# BuzzerWithRelay.net
KiCad netlist of a schematic drawn in Altium Designer
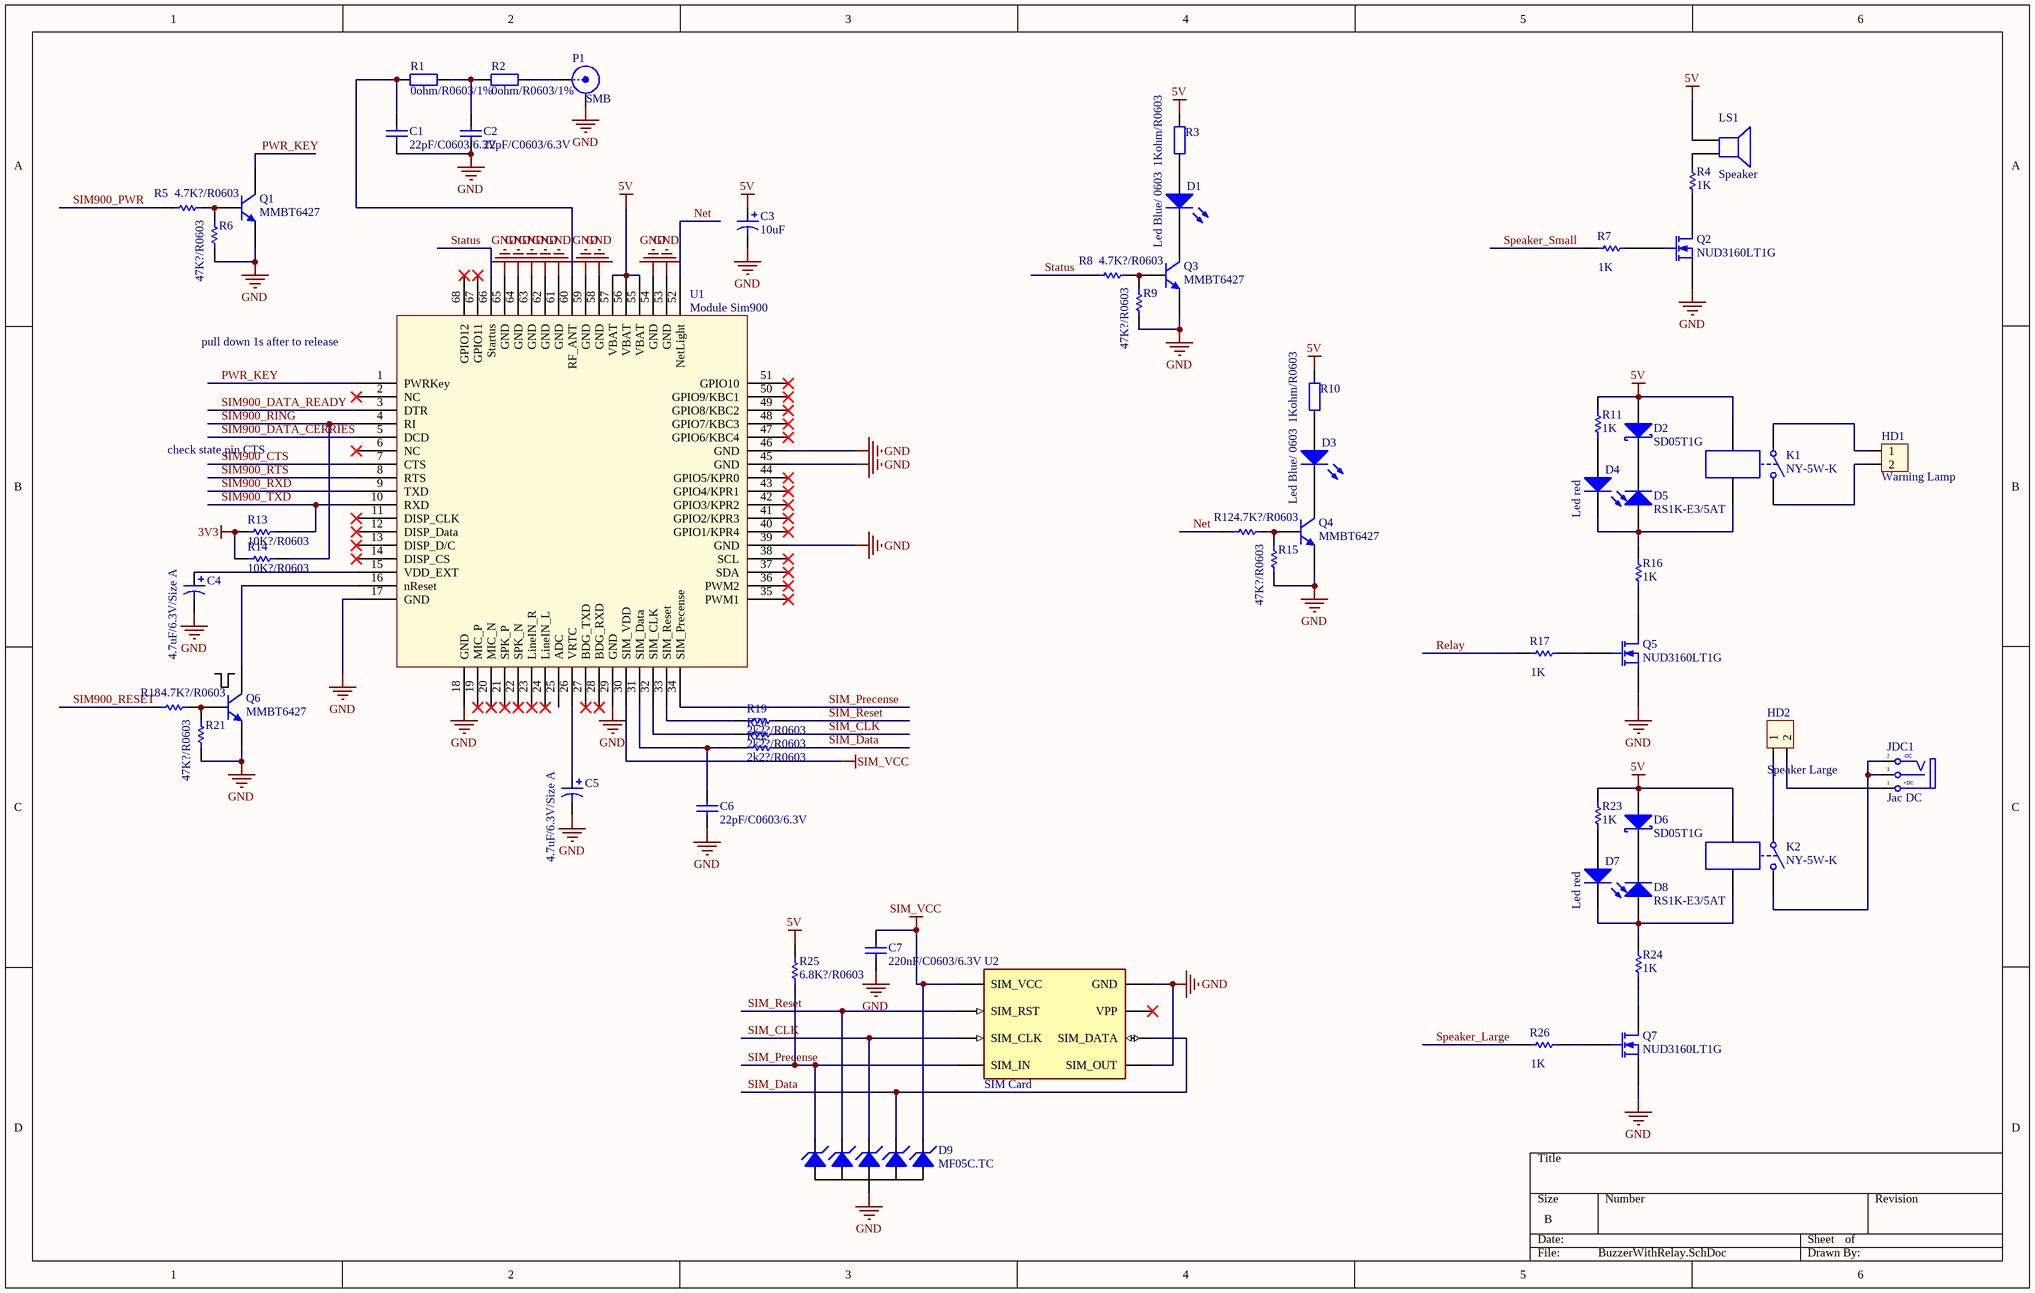
[diagram p0: BuzzerWithRelay.SchDoc]

(export (version "E")
  (design (tool "Eeschema 10.0.6"))
  (components
    (comp (ref "C1")
      (value "22pF/C0603/6.3V")
      (footprint "C0603")
      (description "Capacitor")
      (libsource (lib "Miscellaneous Devices") (part "Cap"))
    )
    (comp (ref "C2")
      (value "22pF/C0603/6.3V")
      (footprint "C0603")
      (description "Capacitor")
      (libsource (lib "Miscellaneous Devices") (part "Cap"))
    )
    (comp (ref "C3")
      (value "10uF")
      (footprint "Cap size A")
      (description "Aluminum Electrolytic Capacitors - Leaded 10uF 25V")
      (fields
        (field (name "MANUFACTURER") "Panasonic")
        (field (name "MANUFACTURER PART NUMBER") "ECA-1EM100")
      )
      (libsource (lib "Manh_Capacitor") (part "10uF/25V/RADIAL 5X11/20%"))
    )
    (comp (ref "C4")
      (value "4.7uF/6.3V/Size A")
      (footprint "Cap size A")
      (description "Polarized Capacitor (Radial)")
      (libsource (lib "Miscellaneous Devices") (part "Cap Pol1"))
    )
    (comp (ref "C5")
      (value "4.7uF/6.3V/Size A")
      (footprint "Cap size A")
      (description "Polarized Capacitor (Radial)")
      (libsource (lib "Miscellaneous Devices") (part "Cap Pol1"))
    )
    (comp (ref "C6")
      (value "22pF/C0603/6.3V")
      (footprint "C0603")
      (description "Capacitor")
      (libsource (lib "Miscellaneous Devices") (part "Cap"))
    )
    (comp (ref "C7")
      (value "220nF/C0603/6.3V")
      (footprint "C0603")
      (description "Capacitor")
      (libsource (lib "Miscellaneous Devices") (part "Cap"))
    )
    (comp (ref "D1")
      (value "Led Blue/ 0603")
      (footprint "led0603")
      (description "Typical INFRARED GaAs LED")
      (libsource (lib "Miscellaneous Devices") (part "LED0"))
    )
    (comp (ref "D2")
      (value "SD05T1G")
      (footprint "DO-214AC")
      (description "Transil")
      (libsource (lib "Tuyen's Library for Altium Designer") (part "Transil"))
    )
    (comp (ref "D3")
      (value "Led Blue/ 0603")
      (footprint "led0603")
      (description "Typical INFRARED GaAs LED")
      (libsource (lib "Miscellaneous Devices") (part "LED0"))
    )
    (comp (ref "D4")
      (value "Led red")
      (footprint "SM-LED-0805-Red")
      (description "Typical INFRARED GaAs LED")
      (libsource (lib "Miscellaneous Devices") (part "LED0"))
    )
    (comp (ref "D5")
      (value "RS1K-E3/5AT")
      (footprint "DO-214AC")
      (description "Default Diode")
      (libsource (lib "Miscellaneous Devices") (part "Diode"))
    )
    (comp (ref "D6")
      (value "SD05T1G")
      (footprint "DO-214AC")
      (description "Transil")
      (libsource (lib "Tuyen's Library for Altium Designer") (part "Transil"))
    )
    (comp (ref "D7")
      (value "Led red")
      (footprint "SM-LED-0805-Red")
      (description "Typical INFRARED GaAs LED")
      (libsource (lib "Miscellaneous Devices") (part "LED0"))
    )
    (comp (ref "D8")
      (value "RS1K-E3/5AT")
      (footprint "DO-214AC")
      (description "Default Diode")
      (libsource (lib "Miscellaneous Devices") (part "Diode"))
    )
    (comp (ref "D9")
      (value "MF05C.TC")
      (footprint "SC70")
      (description "TVS Diode Array  For ESD and Latch-Up Protection")
      (libsource (lib "Tuyens Library for Altium Designer") (part "SMF05C"))
    )
    (comp (ref "HD1")
      (value "Warning Lamp")
      (footprint "HED2")
      (description "Header 2 (Green)")
      (libsource (lib "") (part "Hed2_1"))
    )
    (comp (ref "HD2")
      (value "Speaker Large")
      (footprint "HED2")
      (description "Header 2 (Green)")
      (libsource (lib "syhaunguyen") (part "Hed2"))
    )
    (comp (ref "JDC1")
      (value "Jac DC")
      (footprint "DC-IN")
      (description "Jac DC input")
      (libsource (lib "syhaunguyen") (part "DCIN"))
    )
    (comp (ref "K1")
      (value "NY-5W-K")
      (footprint "Relay NY seri")
      (description "Single-Pole Single-Throw Relay")
      (libsource (lib "Miscellaneous Devices") (part "Relay-SPST"))
    )
    (comp (ref "K2")
      (value "NY-5W-K")
      (footprint "Relay NY seri")
      (description "Single-Pole Single-Throw Relay")
      (libsource (lib "Miscellaneous Devices") (part "Relay-SPST"))
    )
    (comp (ref "LS1")
      (value "Speaker")
      (footprint "Buzzer")
      (description "Loudspeaker")
      (fields (field (name "PUBLISHER") "Altium Limited"))
      (libsource (lib "Tuyens Library for Altium Designer") (part "Speaker"))
    )
    (comp (ref "P1")
      (value "SMB")
      (footprint "atena MM9329-2700")
      (description "SMB Straight Connector")
      (fields (field (name "PUBLISHER") "Altium Limited"))
      (libsource (lib "Miscellaneous Connectors") (part "SMB"))
    )
    (comp (ref "Q1")
      (value "MMBT6427")
      (footprint "SOT 23")
      (description "NPN Bipolar Transistor")
      (libsource (lib "Miscellaneous Devices") (part "NPN"))
    )
    (comp (ref "Q2")
      (value "NUD3160LT1G")
      (footprint "SOT 23")
      (description "SSM3K337R")
      (libsource (lib "Miscellaneous Devices") (part "SSM3K337R"))
    )
    (comp (ref "Q3")
      (value "MMBT6427")
      (footprint "SOT 23")
      (description "NPN Bipolar Transistor")
      (libsource (lib "Miscellaneous Devices") (part "NPN"))
    )
    (comp (ref "Q4")
      (value "MMBT6427")
      (footprint "SOT 23")
      (description "NPN Bipolar Transistor")
      (libsource (lib "Miscellaneous Devices") (part "NPN"))
    )
    (comp (ref "Q5")
      (value "NUD3160LT1G")
      (footprint "SOT 23")
      (description "SSM3K337R")
      (libsource (lib "Miscellaneous Devices") (part "SSM3K337R"))
    )
    (comp (ref "Q6")
      (value "MMBT6427")
      (footprint "SOT 23")
      (description "NPN Bipolar Transistor")
      (libsource (lib "Miscellaneous Devices") (part "NPN"))
    )
    (comp (ref "Q7")
      (value "NUD3160LT1G")
      (footprint "SOT 23")
      (description "SSM3K337R")
      (libsource (lib "Miscellaneous Devices") (part "SSM3K337R"))
    )
    (comp (ref "R1")
      (value "0ohm/R0603/1%")
      (footprint "R0603")
      (description "Resistor")
      (libsource (lib "Miscellaneous Devices") (part "Res2"))
    )
    (comp (ref "R2")
      (value "0ohm/R0603/1%")
      (footprint "R0603")
      (description "Resistor")
      (libsource (lib "Miscellaneous Devices") (part "Res2"))
    )
    (comp (ref "R3")
      (value "1Kohm/R0603")
      (footprint "R0603")
      (description "Resistor")
      (libsource (lib "") (part "Res2_1"))
    )
    (comp (ref "R4")
      (value "1K")
      (footprint "R0603")
      (description "Resistor")
      (fields (field (name "Comment") "Res1") (field (name "PUBLISHER") "Altium Limited"))
      (libsource (lib "Miscellaneous Devices") (part "Res1"))
    )
    (comp (ref "R5")
      (value "4.7K?/R0603")
      (footprint "R0603")
      (description "Resistor")
      (libsource (lib "Miscellaneous Devices") (part "Res1"))
    )
    (comp (ref "R6")
      (value "47K?/R0603")
      (footprint "R0603")
      (description "Resistor")
      (libsource (lib "Miscellaneous Devices") (part "Res1"))
    )
    (comp (ref "R7")
      (value "1K")
      (footprint "R0603")
      (description "Resistor")
      (fields (field (name "Comment") "Res1") (field (name "PUBLISHER") "Altium Limited"))
      (libsource (lib "Miscellaneous Devices") (part "Res1"))
    )
    (comp (ref "R8")
      (value "4.7K?/R0603")
      (footprint "R0603")
      (description "Resistor")
      (libsource (lib "Miscellaneous Devices") (part "Res1"))
    )
    (comp (ref "R9")
      (value "47K?/R0603")
      (footprint "R0603")
      (description "Resistor")
      (libsource (lib "Miscellaneous Devices") (part "Res1"))
    )
    (comp (ref "R10")
      (value "1Kohm/R0603")
      (footprint "R0603")
      (description "Resistor")
      (libsource (lib "") (part "Res2_1"))
    )
    (comp (ref "R11")
      (value "1K")
      (footprint "SM-RES-0805")
      (description "Resistor")
      (fields (field (name "Comment") "Res1") (field (name "PUBLISHER") "Altium Limited"))
      (libsource (lib "Miscellaneous Devices") (part "Res1"))
    )
    (comp (ref "R12")
      (value "4.7K?/R0603")
      (footprint "R0603")
      (description "Resistor")
      (libsource (lib "Miscellaneous Devices") (part "Res1"))
    )
    (comp (ref "R13")
      (value "10K?/R0603")
      (footprint "R0603")
      (description "Resistor")
      (libsource (lib "Miscellaneous Devices") (part "Res1"))
    )
    (comp (ref "R14")
      (value "10K?/R0603")
      (footprint "R0603")
      (description "Resistor")
      (libsource (lib "Miscellaneous Devices") (part "Res1"))
    )
    (comp (ref "R15")
      (value "47K?/R0603")
      (footprint "R0603")
      (description "Resistor")
      (libsource (lib "Miscellaneous Devices") (part "Res1"))
    )
    (comp (ref "R16")
      (value "1K")
      (footprint "SM-RES-0805")
      (description "Resistor")
      (fields (field (name "Comment") "Res1") (field (name "PUBLISHER") "Altium Limited"))
      (libsource (lib "Miscellaneous Devices") (part "Res1"))
    )
    (comp (ref "R17")
      (value "1K")
      (footprint "SM-RES-0805")
      (description "Resistor")
      (fields (field (name "Comment") "Res1") (field (name "PUBLISHER") "Altium Limited"))
      (libsource (lib "Miscellaneous Devices") (part "Res1"))
    )
    (comp (ref "R18")
      (value "4.7K?/R0603")
      (footprint "R0603")
      (description "Resistor")
      (libsource (lib "Miscellaneous Devices") (part "Res1"))
    )
    (comp (ref "R19")
      (value "2k2?/R0603")
      (footprint "R0603")
      (description "Resistor")
      (libsource (lib "Miscellaneous Devices") (part "Res1"))
    )
    (comp (ref "R20")
      (value "2k2?/R0603")
      (footprint "R0603")
      (description "Resistor")
      (libsource (lib "Miscellaneous Devices") (part "Res1"))
    )
    (comp (ref "R21")
      (value "47K?/R0603")
      (footprint "R0603")
      (description "Resistor")
      (libsource (lib "Miscellaneous Devices") (part "Res1"))
    )
    (comp (ref "R22")
      (value "2k2?/R0603")
      (footprint "R0603")
      (description "Resistor")
      (libsource (lib "Miscellaneous Devices") (part "Res1"))
    )
    (comp (ref "R23")
      (value "1K")
      (footprint "SM-RES-0805")
      (description "Resistor")
      (fields (field (name "Comment") "Res1") (field (name "PUBLISHER") "Altium Limited"))
      (libsource (lib "Miscellaneous Devices") (part "Res1"))
    )
    (comp (ref "R24")
      (value "1K")
      (footprint "SM-RES-0805")
      (description "Resistor")
      (fields (field (name "Comment") "Res1") (field (name "PUBLISHER") "Altium Limited"))
      (libsource (lib "Miscellaneous Devices") (part "Res1"))
    )
    (comp (ref "R25")
      (value "6.8K?/R0603")
      (footprint "R0603")
      (description "Resistor")
      (libsource (lib "Miscellaneous Devices") (part "Res1"))
    )
    (comp (ref "R26")
      (value "1K")
      (footprint "SM-RES-0805")
      (description "Resistor")
      (fields (field (name "Comment") "Res1") (field (name "PUBLISHER") "Altium Limited"))
      (libsource (lib "Miscellaneous Devices") (part "Res1"))
    )
    (comp (ref "U1")
      (value "Module Sim900")
      (footprint "Sim900")
      (description "GSM-GPRS")
      (libsource (lib "Tuyens Library for Altium Designer") (part "SIM900"))
    )
    (comp (ref "U2")
      (value "SIM Card")
      (footprint "SIMCARD")
      (description "Sim Card")
      (libsource (lib "Tuyens Library for Altium Designer") (part "SIM Card"))
    )
  )
  (nets
    (net (code "1") (name "/Net") (class "Default")
      (node (ref "R12") (pin "1") (pinfunction "1_1") (pintype "passive"))
      (node (ref "U1") (pin "52") (pinfunction "NetLight_52") (pintype "passive"))
    )
    (net (code "2") (name "/PWR_KEY") (class "Default")
      (node (ref "Q1") (pin "3") (pinfunction "C_3") (pintype "passive"))
      (node (ref "U1") (pin "1") (pinfunction "PWRKey_1") (pintype "passive"))
    )
    (net (code "3") (name "/Relay") (class "Default")
      (node (ref "R17") (pin "1") (pinfunction "1_1") (pintype "passive"))
    )
    (net (code "4") (name "/SIM900_CTS") (class "Default")
      (node (ref "U1") (pin "7") (pinfunction "CTS_7") (pintype "passive"))
    )
    (net (code "5") (name "/SIM900_DATA_CERRIES") (class "Default")
      (node (ref "U1") (pin "5") (pinfunction "DCD_5") (pintype "passive"))
    )
    (net (code "6") (name "/SIM900_DATA_READY") (class "Default")
      (node (ref "U1") (pin "3") (pinfunction "DTR_3") (pintype "passive"))
    )
    (net (code "7") (name "/SIM900_PWR") (class "Default")
      (node (ref "R5") (pin "1") (pinfunction "1_1") (pintype "passive"))
    )
    (net (code "8") (name "/SIM900_RESET") (class "Default")
      (node (ref "R18") (pin "1") (pinfunction "1_1") (pintype "passive"))
    )
    (net (code "9") (name "/SIM900_RING") (class "Default")
      (node (ref "R14") (pin "2") (pinfunction "2_2") (pintype "passive"))
      (node (ref "U1") (pin "4") (pinfunction "RI_4") (pintype "passive"))
    )
    (net (code "10") (name "/SIM900_RTS") (class "Default")
      (node (ref "U1") (pin "8") (pinfunction "RTS_8") (pintype "passive"))
    )
    (net (code "11") (name "/SIM900_RXD") (class "Default")
      (node (ref "U1") (pin "9") (pinfunction "TXD_9") (pintype "passive"))
    )
    (net (code "12") (name "/SIM900_TXD") (class "Default")
      (node (ref "R13") (pin "2") (pinfunction "2_2") (pintype "passive"))
      (node (ref "U1") (pin "10") (pinfunction "RXD_10") (pintype "passive"))
    )
    (net (code "13") (name "/SIM_CLK") (class "Default")
      (node (ref "D9") (pin "4") (pinfunction "K_4") (pintype "passive"))
      (node (ref "R20") (pin "1") (pinfunction "1_1") (pintype "passive"))
      (node (ref "U2") (pin "C3") (pinfunction "SIM_CLK_C3") (pintype "input"))
    )
    (net (code "14") (name "/SIM_Data") (class "Default")
      (node (ref "D9") (pin "5") (pinfunction "K_5") (pintype "passive"))
      (node (ref "R22") (pin "1") (pinfunction "1_1") (pintype "passive"))
      (node (ref "U2") (pin "C7") (pinfunction "SIM_DATA_C7") (pintype "bidirectional"))
    )
    (net (code "15") (name "/SIM_Precense") (class "Default")
      (node (ref "D9") (pin "1") (pinfunction "K_1") (pintype "passive"))
      (node (ref "R25") (pin "2") (pinfunction "2_2") (pintype "passive"))
      (node (ref "U1") (pin "34") (pinfunction "SIM_Precense_34") (pintype "passive"))
      (node (ref "U2") (pin "C4") (pinfunction "SIM_IN_C4") (pintype "passive"))
    )
    (net (code "16") (name "/SIM_Reset") (class "Default")
      (node (ref "D9") (pin "3") (pinfunction "K_3") (pintype "passive"))
      (node (ref "R19") (pin "1") (pinfunction "1_1") (pintype "passive"))
      (node (ref "U2") (pin "C2") (pinfunction "SIM_RST_C2") (pintype "input"))
    )
    (net (code "17") (name "/Speaker_Large") (class "Default")
      (node (ref "R26") (pin "1") (pinfunction "1_1") (pintype "passive"))
    )
    (net (code "18") (name "/Speaker_Small") (class "Default")
      (node (ref "R7") (pin "1") (pinfunction "1_1") (pintype "passive"))
    )
    (net (code "19") (name "/Status") (class "Default")
      (node (ref "R8") (pin "1") (pinfunction "1_1") (pintype "passive"))
      (node (ref "U1") (pin "66") (pinfunction "Startus_66") (pintype "passive"))
    )
    (net (code "20") (name "3V3") (class "Default")
      (node (ref "R13") (pin "1") (pinfunction "1_1") (pintype "passive"))
      (node (ref "R14") (pin "1") (pinfunction "1_1") (pintype "passive"))
    )
    (net (code "21") (name "5V") (class "Default")
      (node (ref "C3") (pin "1") (pinfunction "+_1") (pintype "passive"))
      (node (ref "D2") (pin "2") (pinfunction "2_2") (pintype "passive"))
      (node (ref "D6") (pin "2") (pinfunction "2_2") (pintype "passive"))
      (node (ref "K1") (pin "3") (pinfunction "3_3") (pintype "passive"))
      (node (ref "K2") (pin "3") (pinfunction "3_3") (pintype "passive"))
      (node (ref "LS1") (pin "+") (pinfunction "+_+") (pintype "passive"))
      (node (ref "R10") (pin "2") (pinfunction "2_2") (pintype "passive"))
      (node (ref "R11") (pin "2") (pinfunction "2_2") (pintype "passive"))
      (node (ref "R23") (pin "2") (pinfunction "2_2") (pintype "passive"))
      (node (ref "R25") (pin "1") (pinfunction "1_1") (pintype "passive"))
      (node (ref "R3") (pin "2") (pinfunction "2_2") (pintype "passive"))
      (node (ref "U1") (pin "55") (pinfunction "VBAT_55") (pintype "passive"))
      (node (ref "U1") (pin "56") (pinfunction "VBAT_56") (pintype "passive"))
      (node (ref "U1") (pin "57") (pinfunction "VBAT_57") (pintype "passive"))
    )
    (net (code "22") (name "GND") (class "Default")
      (node (ref "C1") (pin "1") (pinfunction "1_1") (pintype "passive"))
      (node (ref "C2") (pin "1") (pinfunction "1_1") (pintype "passive"))
      (node (ref "C3") (pin "2") (pinfunction "-_2") (pintype "passive"))
      (node (ref "C4") (pin "2") (pinfunction "2_2") (pintype "passive"))
      (node (ref "C5") (pin "2") (pinfunction "2_2") (pintype "passive"))
      (node (ref "C6") (pin "1") (pinfunction "1_1") (pintype "passive"))
      (node (ref "C7") (pin "1") (pinfunction "1_1") (pintype "passive"))
      (node (ref "D9") (pin "2") (pinfunction "K_2") (pintype "passive"))
      (node (ref "P1") (pin "2") (pinfunction "Y_2") (pintype "passive"))
      (node (ref "Q1") (pin "2") (pinfunction "E_2") (pintype "passive"))
      (node (ref "Q2") (pin "2") (pinfunction "S_2") (pintype "passive"))
      (node (ref "Q3") (pin "2") (pinfunction "E_2") (pintype "passive"))
      (node (ref "Q4") (pin "2") (pinfunction "E_2") (pintype "passive"))
      (node (ref "Q5") (pin "2") (pinfunction "S_2") (pintype "passive"))
      (node (ref "Q6") (pin "2") (pinfunction "E_2") (pintype "passive"))
      (node (ref "Q7") (pin "2") (pinfunction "S_2") (pintype "passive"))
      (node (ref "R15") (pin "1") (pinfunction "1_1") (pintype "passive"))
      (node (ref "R21") (pin "1") (pinfunction "1_1") (pintype "passive"))
      (node (ref "R6") (pin "1") (pinfunction "1_1") (pintype "passive"))
      (node (ref "R9") (pin "1") (pinfunction "1_1") (pintype "passive"))
      (node (ref "U1") (pin "17") (pinfunction "GND_17") (pintype "passive"))
      (node (ref "U1") (pin "18") (pinfunction "GND_18") (pintype "passive"))
      (node (ref "U1") (pin "29") (pinfunction "GND_29") (pintype "passive"))
      (node (ref "U1") (pin "39") (pinfunction "GND_39") (pintype "passive"))
      (node (ref "U1") (pin "45") (pinfunction "GND_45") (pintype "passive"))
      (node (ref "U1") (pin "46") (pinfunction "GND_46") (pintype "passive"))
      (node (ref "U1") (pin "53") (pinfunction "GND_53") (pintype "passive"))
      (node (ref "U1") (pin "54") (pinfunction "GND_54") (pintype "passive"))
      (node (ref "U1") (pin "58") (pinfunction "GND_58") (pintype "passive"))
      (node (ref "U1") (pin "59") (pinfunction "GND_59") (pintype "passive"))
      (node (ref "U1") (pin "61") (pinfunction "GND_61") (pintype "passive"))
      (node (ref "U1") (pin "62") (pinfunction "GND_62") (pintype "passive"))
      (node (ref "U1") (pin "63") (pinfunction "GND_63") (pintype "passive"))
      (node (ref "U1") (pin "64") (pinfunction "GND_64") (pintype "passive"))
      (node (ref "U1") (pin "65") (pinfunction "GND_65") (pintype "passive"))
      (node (ref "U2") (pin "C5") (pinfunction "GND_C5") (pintype "power_in"))
      (node (ref "U2") (pin "C8") (pinfunction "SIM_OUT_C8") (pintype "passive"))
    )
    (net (code "23") (name "Net-(C2-Pad2)") (class "Default")
      (node (ref "C2") (pin "2") (pinfunction "2_2") (pintype "passive"))
      (node (ref "R1") (pin "1") (pinfunction "1_1") (pintype "passive"))
      (node (ref "R2") (pin "2") (pinfunction "2_2") (pintype "passive"))
    )
    (net (code "24") (name "Net-(D1-A)") (class "Default")
      (node (ref "D1") (pin "1") (pinfunction "A_1") (pintype "passive"))
      (node (ref "R3") (pin "1") (pinfunction "1_1") (pintype "passive"))
    )
    (net (code "25") (name "Net-(D1-K)") (class "Default")
      (node (ref "D1") (pin "2") (pinfunction "K_2") (pintype "passive"))
      (node (ref "Q3") (pin "3") (pinfunction "C_3") (pintype "passive"))
    )
    (net (code "26") (name "Net-(D3-A)") (class "Default")
      (node (ref "D3") (pin "1") (pinfunction "A_1") (pintype "passive"))
      (node (ref "R10") (pin "1") (pinfunction "1_1") (pintype "passive"))
    )
    (net (code "27") (name "Net-(D3-K)") (class "Default")
      (node (ref "D3") (pin "2") (pinfunction "K_2") (pintype "passive"))
      (node (ref "Q4") (pin "3") (pinfunction "C_3") (pintype "passive"))
    )
    (net (code "28") (name "Net-(D4-A)") (class "Default")
      (node (ref "D4") (pin "1") (pinfunction "A_1") (pintype "passive"))
      (node (ref "R11") (pin "1") (pinfunction "1_1") (pintype "passive"))
    )
    (net (code "29") (name "Net-(D4-K)") (class "Default")
      (node (ref "D4") (pin "2") (pinfunction "K_2") (pintype "passive"))
      (node (ref "D5") (pin "1") (pinfunction "A_1") (pintype "passive"))
      (node (ref "K1") (pin "4") (pinfunction "4_4") (pintype "passive"))
      (node (ref "R16") (pin "2") (pinfunction "2_2") (pintype "passive"))
    )
    (net (code "30") (name "Net-(D5-K)") (class "Default")
      (node (ref "D2") (pin "1") (pinfunction "1_1") (pintype "passive"))
      (node (ref "D5") (pin "2") (pinfunction "K_2") (pintype "passive"))
    )
    (net (code "31") (name "Net-(D7-A)") (class "Default")
      (node (ref "D7") (pin "1") (pinfunction "A_1") (pintype "passive"))
      (node (ref "R23") (pin "1") (pinfunction "1_1") (pintype "passive"))
    )
    (net (code "32") (name "Net-(D7-K)") (class "Default")
      (node (ref "D7") (pin "2") (pinfunction "K_2") (pintype "passive"))
      (node (ref "D8") (pin "1") (pinfunction "A_1") (pintype "passive"))
      (node (ref "K2") (pin "4") (pinfunction "4_4") (pintype "passive"))
      (node (ref "R24") (pin "2") (pinfunction "2_2") (pintype "passive"))
    )
    (net (code "33") (name "Net-(D8-K)") (class "Default")
      (node (ref "D6") (pin "1") (pinfunction "1_1") (pintype "passive"))
      (node (ref "D8") (pin "2") (pinfunction "K_2") (pintype "passive"))
    )
    (net (code "34") (name "Net-(HD1-Pad1)") (class "Default")
      (node (ref "HD1") (pin "1") (pinfunction "1_1") (pintype "passive"))
      (node (ref "K1") (pin "1") (pinfunction "1_1") (pintype "passive"))
    )
    (net (code "35") (name "Net-(HD1-Pad2)") (class "Default")
      (node (ref "HD1") (pin "2") (pinfunction "2_2") (pintype "passive"))
      (node (ref "K1") (pin "2") (pinfunction "2_2") (pintype "passive"))
    )
    (net (code "36") (name "Net-(HD2-Pad1)") (class "Default")
      (node (ref "HD2") (pin "1") (pinfunction "1_1") (pintype "passive"))
      (node (ref "K2") (pin "1") (pinfunction "1_1") (pintype "passive"))
    )
    (net (code "37") (name "Net-(JDC1-S)") (class "Default")
      (node (ref "JDC1") (pin "2") (pinfunction "TN_2") (pintype "passive"))
      (node (ref "JDC1") (pin "3") (pinfunction "S_3") (pintype "power_in"))
      (node (ref "K2") (pin "2") (pinfunction "2_2") (pintype "passive"))
    )
    (net (code "38") (name "Net-(JDC1-T)") (class "Default")
      (node (ref "HD2") (pin "2") (pinfunction "2_2") (pintype "passive"))
      (node (ref "JDC1") (pin "1") (pinfunction "T_1") (pintype "passive"))
    )
    (net (code "39") (name "Net-(LS1-Pad-)") (class "Default")
      (node (ref "LS1") (pin "-") (pinfunction "-_-") (pintype "passive"))
      (node (ref "R4") (pin "2") (pinfunction "2_2") (pintype "passive"))
    )
    (net (code "40") (name "Net-(P1-X)") (class "Default")
      (node (ref "P1") (pin "1") (pinfunction "X_1") (pintype "passive"))
      (node (ref "R2") (pin "1") (pinfunction "1_1") (pintype "passive"))
    )
    (net (code "41") (name "Net-(Q1-B)") (class "Default")
      (node (ref "Q1") (pin "1") (pinfunction "B_1") (pintype "passive"))
      (node (ref "R5") (pin "2") (pinfunction "2_2") (pintype "passive"))
      (node (ref "R6") (pin "2") (pinfunction "2_2") (pintype "passive"))
    )
    (net (code "42") (name "Net-(Q2-D)") (class "Default")
      (node (ref "Q2") (pin "3") (pinfunction "D_3") (pintype "passive"))
      (node (ref "R4") (pin "1") (pinfunction "1_1") (pintype "passive"))
    )
    (net (code "43") (name "Net-(Q2-G)") (class "Default")
      (node (ref "Q2") (pin "1") (pinfunction "G_1") (pintype "passive"))
      (node (ref "R7") (pin "2") (pinfunction "2_2") (pintype "passive"))
    )
    (net (code "44") (name "Net-(Q3-B)") (class "Default")
      (node (ref "Q3") (pin "1") (pinfunction "B_1") (pintype "passive"))
      (node (ref "R8") (pin "2") (pinfunction "2_2") (pintype "passive"))
      (node (ref "R9") (pin "2") (pinfunction "2_2") (pintype "passive"))
    )
    (net (code "45") (name "Net-(Q4-B)") (class "Default")
      (node (ref "Q4") (pin "1") (pinfunction "B_1") (pintype "passive"))
      (node (ref "R12") (pin "2") (pinfunction "2_2") (pintype "passive"))
      (node (ref "R15") (pin "2") (pinfunction "2_2") (pintype "passive"))
    )
    (net (code "46") (name "Net-(Q5-D)") (class "Default")
      (node (ref "Q5") (pin "3") (pinfunction "D_3") (pintype "passive"))
      (node (ref "R16") (pin "1") (pinfunction "1_1") (pintype "passive"))
    )
    (net (code "47") (name "Net-(Q5-G)") (class "Default")
      (node (ref "Q5") (pin "1") (pinfunction "G_1") (pintype "passive"))
      (node (ref "R17") (pin "2") (pinfunction "2_2") (pintype "passive"))
    )
    (net (code "48") (name "Net-(Q6-B)") (class "Default")
      (node (ref "Q6") (pin "1") (pinfunction "B_1") (pintype "passive"))
      (node (ref "R18") (pin "2") (pinfunction "2_2") (pintype "passive"))
      (node (ref "R21") (pin "2") (pinfunction "2_2") (pintype "passive"))
    )
    (net (code "49") (name "Net-(Q6-C)") (class "Default")
      (node (ref "Q6") (pin "3") (pinfunction "C_3") (pintype "passive"))
      (node (ref "U1") (pin "16") (pinfunction "nReset_16") (pintype "passive"))
    )
    (net (code "50") (name "Net-(Q7-D)") (class "Default")
      (node (ref "Q7") (pin "3") (pinfunction "D_3") (pintype "passive"))
      (node (ref "R24") (pin "1") (pinfunction "1_1") (pintype "passive"))
    )
    (net (code "51") (name "Net-(Q7-G)") (class "Default")
      (node (ref "Q7") (pin "1") (pinfunction "G_1") (pintype "passive"))
      (node (ref "R26") (pin "2") (pinfunction "2_2") (pintype "passive"))
    )
    (net (code "52") (name "Net-(U1-RF_ANT)") (class "Default")
      (node (ref "C1") (pin "2") (pinfunction "2_2") (pintype "passive"))
      (node (ref "R1") (pin "2") (pinfunction "2_2") (pintype "passive"))
      (node (ref "U1") (pin "60") (pinfunction "RF_ANT_60") (pintype "passive"))
    )
    (net (code "53") (name "Net-(U1-SIM_CLK)") (class "Default")
      (node (ref "R20") (pin "2") (pinfunction "2_2") (pintype "passive"))
      (node (ref "U1") (pin "32") (pinfunction "SIM_CLK_32") (pintype "passive"))
    )
    (net (code "54") (name "Net-(U1-SIM_Data)") (class "Default")
      (node (ref "C6") (pin "2") (pinfunction "2_2") (pintype "passive"))
      (node (ref "R22") (pin "2") (pinfunction "2_2") (pintype "passive"))
      (node (ref "U1") (pin "31") (pinfunction "SIM_Data_31") (pintype "passive"))
    )
    (net (code "55") (name "Net-(U1-SIM_Reset)") (class "Default")
      (node (ref "R19") (pin "2") (pinfunction "2_2") (pintype "passive"))
      (node (ref "U1") (pin "33") (pinfunction "SIM_Reset_33") (pintype "passive"))
    )
    (net (code "56") (name "Net-(U1-VDD_EXT)") (class "Default")
      (node (ref "C4") (pin "1") (pinfunction "1_1") (pintype "passive"))
      (node (ref "U1") (pin "15") (pinfunction "VDD_EXT_15") (pintype "passive"))
    )
    (net (code "57") (name "Net-(U1-VRTC)") (class "Default")
      (node (ref "C5") (pin "1") (pinfunction "1_1") (pintype "passive"))
      (node (ref "U1") (pin "26") (pinfunction "VRTC_26") (pintype "passive"))
    )
    (net (code "58") (name "SIM_VCC") (class "Default")
      (node (ref "C7") (pin "2") (pinfunction "2_2") (pintype "passive"))
      (node (ref "D9") (pin "6") (pinfunction "K_6") (pintype "passive"))
      (node (ref "U1") (pin "30") (pinfunction "SIM_VDD_30") (pintype "passive"))
      (node (ref "U2") (pin "C1") (pinfunction "SIM_VCC_C1") (pintype "power_in"))
    )
    (net (code "59") (name "unconnected-(U1-ADC-Pad25)") (class "Default")
      (node (ref "U1") (pin "25") (pinfunction "ADC_25") (pintype "passive"))
    )
    (net (code "60") (name "unconnected-(U1-BDG_RXD-Pad28)") (class "Default")
      (node (ref "U1") (pin "28") (pinfunction "BDG_RXD_28") (pintype "passive+no_connect"))
    )
    (net (code "61") (name "unconnected-(U1-BDG_TXD-Pad27)") (class "Default")
      (node (ref "U1") (pin "27") (pinfunction "BDG_TXD_27") (pintype "passive+no_connect"))
    )
    (net (code "62") (name "unconnected-(U1-DISP_CLK-Pad11)") (class "Default")
      (node (ref "U1") (pin "11") (pinfunction "DISP_CLK_11") (pintype "passive+no_connect"))
    )
    (net (code "63") (name "unconnected-(U1-DISP_CS-Pad14)") (class "Default")
      (node (ref "U1") (pin "14") (pinfunction "DISP_CS_14") (pintype "passive+no_connect"))
    )
    (net (code "64") (name "unconnected-(U1-DISP_Data-Pad12)") (class "Default")
      (node (ref "U1") (pin "12") (pinfunction "DISP_Data_12") (pintype "passive+no_connect"))
    )
    (net (code "65") (name "unconnected-(U1-DISP_D{slash}C-Pad13)") (class "Default")
      (node (ref "U1") (pin "13") (pinfunction "DISP_D/C_13") (pintype "passive+no_connect"))
    )
    (net (code "66") (name "unconnected-(U1-GPIO1{slash}KPR4-Pad40)") (class "Default")
      (node (ref "U1") (pin "40") (pinfunction "GPIO1/KPR4_40") (pintype "passive+no_connect"))
    )
    (net (code "67") (name "unconnected-(U1-GPIO2{slash}KPR3-Pad41)") (class "Default")
      (node (ref "U1") (pin "41") (pinfunction "GPIO2/KPR3_41") (pintype "passive+no_connect"))
    )
    (net (code "68") (name "unconnected-(U1-GPIO3{slash}KPR2-Pad42)") (class "Default")
      (node (ref "U1") (pin "42") (pinfunction "GPIO3/KPR2_42") (pintype "passive+no_connect"))
    )
    (net (code "69") (name "unconnected-(U1-GPIO4{slash}KPR1-Pad43)") (class "Default")
      (node (ref "U1") (pin "43") (pinfunction "GPIO4/KPR1_43") (pintype "passive+no_connect"))
    )
    (net (code "70") (name "unconnected-(U1-GPIO5{slash}KPR0-Pad44)") (class "Default")
      (node (ref "U1") (pin "44") (pinfunction "GPIO5/KPR0_44") (pintype "passive+no_connect"))
    )
    (net (code "71") (name "unconnected-(U1-GPIO6{slash}KBC4-Pad47)") (class "Default")
      (node (ref "U1") (pin "47") (pinfunction "GPIO6/KBC4_47") (pintype "passive+no_connect"))
    )
    (net (code "72") (name "unconnected-(U1-GPIO7{slash}KBC3-Pad48)") (class "Default")
      (node (ref "U1") (pin "48") (pinfunction "GPIO7/KBC3_48") (pintype "passive+no_connect"))
    )
    (net (code "73") (name "unconnected-(U1-GPIO8{slash}KBC2-Pad49)") (class "Default")
      (node (ref "U1") (pin "49") (pinfunction "GPIO8/KBC2_49") (pintype "passive+no_connect"))
    )
    (net (code "74") (name "unconnected-(U1-GPIO9{slash}KBC1-Pad50)") (class "Default")
      (node (ref "U1") (pin "50") (pinfunction "GPIO9/KBC1_50") (pintype "passive+no_connect"))
    )
    (net (code "75") (name "unconnected-(U1-GPIO10-Pad51)") (class "Default")
      (node (ref "U1") (pin "51") (pinfunction "GPIO10_51") (pintype "passive+no_connect"))
    )
    (net (code "76") (name "unconnected-(U1-GPIO11-Pad67)") (class "Default")
      (node (ref "U1") (pin "67") (pinfunction "GPIO11_67") (pintype "passive+no_connect"))
    )
    (net (code "77") (name "unconnected-(U1-GPIO12-Pad68)") (class "Default")
      (node (ref "U1") (pin "68") (pinfunction "GPIO12_68") (pintype "passive+no_connect"))
    )
    (net (code "78") (name "unconnected-(U1-LineIN_L-Pad24)") (class "Default")
      (node (ref "U1") (pin "24") (pinfunction "LineIN_L_24") (pintype "passive+no_connect"))
    )
    (net (code "79") (name "unconnected-(U1-LineIN_R-Pad23)") (class "Default")
      (node (ref "U1") (pin "23") (pinfunction "LineIN_R_23") (pintype "passive+no_connect"))
    )
    (net (code "80") (name "unconnected-(U1-MIC_N-Pad20)") (class "Default")
      (node (ref "U1") (pin "20") (pinfunction "MIC_N_20") (pintype "passive+no_connect"))
    )
    (net (code "81") (name "unconnected-(U1-MIC_P-Pad19)") (class "Default")
      (node (ref "U1") (pin "19") (pinfunction "MIC_P_19") (pintype "passive+no_connect"))
    )
    (net (code "82") (name "unconnected-(U1-NC-Pad2)") (class "Default")
      (node (ref "U1") (pin "2") (pinfunction "NC_2") (pintype "passive+no_connect"))
    )
    (net (code "83") (name "unconnected-(U1-NC-Pad6)") (class "Default")
      (node (ref "U1") (pin "6") (pinfunction "NC_6") (pintype "passive+no_connect"))
    )
    (net (code "84") (name "unconnected-(U1-PWM1-Pad35)") (class "Default")
      (node (ref "U1") (pin "35") (pinfunction "PWM1_35") (pintype "passive+no_connect"))
    )
    (net (code "85") (name "unconnected-(U1-PWM2-Pad36)") (class "Default")
      (node (ref "U1") (pin "36") (pinfunction "PWM2_36") (pintype "passive+no_connect"))
    )
    (net (code "86") (name "unconnected-(U1-SCL-Pad38)") (class "Default")
      (node (ref "U1") (pin "38") (pinfunction "SCL_38") (pintype "passive+no_connect"))
    )
    (net (code "87") (name "unconnected-(U1-SDA-Pad37)") (class "Default")
      (node (ref "U1") (pin "37") (pinfunction "SDA_37") (pintype "passive+no_connect"))
    )
    (net (code "88") (name "unconnected-(U1-SPK_N-Pad22)") (class "Default")
      (node (ref "U1") (pin "22") (pinfunction "SPK_N_22") (pintype "passive+no_connect"))
    )
    (net (code "89") (name "unconnected-(U1-SPK_P-Pad21)") (class "Default")
      (node (ref "U1") (pin "21") (pinfunction "SPK_P_21") (pintype "passive+no_connect"))
    )
    (net (code "90") (name "unconnected-(U2-VPP-PadC6)") (class "Default")
      (node (ref "U2") (pin "C6") (pinfunction "VPP_C6") (pintype "passive+no_connect"))
    )
  )
)
